# Voltage_Monitor.net
KiCad netlist of a schematic drawn in Altium Designer
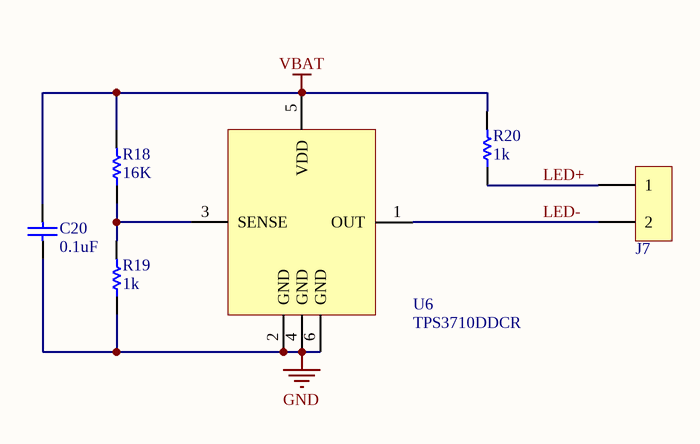
[diagram p0: Voltage Monitor.SchDoc]

(export (version "E")
  (design (tool "Eeschema 10.0.6"))
  (components
    (comp (ref "C20")
      (value "0.1uF")
      (footprint "CAPC1608X09N")
      (fields
        (field (name "DIGIKEY PART NUMBER") "490-1519-1-ND")
        (field (name "VOLTAGE") "50V")
        (field (name "TOLERANCE") "10%")
      )
      (libsource (lib "Speaker Library") (part "CAP CER 0.1uF 0603"))
    )
    (comp (ref "J7")
      (value "2POS THRU HOLE 2.54MM")
      (footprint "2POS Through Hole 2.54MM")
      (libsource (lib "Speaker Library") (part "2POS THRU HOLE 2.54MM"))
    )
    (comp (ref "R18")
      (value "16K")
      (footprint "RESC1608X06N")
      (fields
        (field (name "TOLERANCE") "1%")
        (field (name "DIGIKEY PART NUMBER") "311-16KGRCT-ND")
        (field (name "MANUFACTURER") "Yageo")
      )
      (libsource (lib "Speaker Library") (part "RES 16K 0603"))
    )
    (comp (ref "R19")
      (value "1k")
      (footprint "RESC1608X06N")
      (fields
        (field (name "TOLERANCE") "1%")
        (field (name "POWER") "0.25W")
        (field (name "MANUFACTURER") "Panasonic")
      )
      (libsource (lib "Speaker Library") (part "RES 1K 0603"))
    )
    (comp (ref "R20")
      (value "1k")
      (footprint "RESC1608X06N")
      (fields
        (field (name "TOLERANCE") "1%")
        (field (name "POWER") "0.25W")
        (field (name "MANUFACTURER") "Panasonic")
      )
      (libsource (lib "Speaker Library") (part "RES 1K 0603"))
    )
    (comp (ref "U6")
      (value "TPS3710DDCR")
      (footprint "SOT95P280X110-6N (DDC)")
      (description "Voltage Monitor, 400mV, Open Drain")
      (fields
        (field (name "MANUFACTURER") "Texas Instruments")
        (field (name "DIGIKEY PART NUMBER") "296-43105-1-ND")
      )
      (libsource (lib "Speaker Library") (part "TPS3710DDCR"))
    )
  )
  (nets
    (net (code "1") (name "/LED+") (class "Default")
      (node (ref "J7") (pin "1") (pinfunction "1_1") (pintype "passive"))
      (node (ref "R20") (pin "1") (pinfunction "1_1") (pintype "passive"))
    )
    (net (code "2") (name "/LED-") (class "Default")
      (node (ref "J7") (pin "2") (pinfunction "2_2") (pintype "passive"))
      (node (ref "U6") (pin "1") (pinfunction "OUT_1") (pintype "passive"))
    )
    (net (code "3") (name "GND") (class "Default")
      (node (ref "C20") (pin "1") (pinfunction "1_1") (pintype "passive"))
      (node (ref "R19") (pin "1") (pinfunction "1_1") (pintype "passive"))
      (node (ref "U6") (pin "2") (pinfunction "GND_2") (pintype "power_in"))
      (node (ref "U6") (pin "4") (pinfunction "GND_4") (pintype "power_in"))
      (node (ref "U6") (pin "6") (pinfunction "GND_6") (pintype "power_in"))
    )
    (net (code "4") (name "Net-(U6-SENSE)") (class "Default")
      (node (ref "R18") (pin "1") (pinfunction "1_1") (pintype "passive"))
      (node (ref "R19") (pin "2") (pinfunction "2_2") (pintype "passive"))
      (node (ref "U6") (pin "3") (pinfunction "SENSE_3") (pintype "passive"))
    )
    (net (code "5") (name "VBAT") (class "Default")
      (node (ref "C20") (pin "2") (pinfunction "2_2") (pintype "passive"))
      (node (ref "R18") (pin "2") (pinfunction "2_2") (pintype "passive"))
      (node (ref "R20") (pin "2") (pinfunction "2_2") (pintype "passive"))
      (node (ref "U6") (pin "5") (pinfunction "VDD_5") (pintype "power_in"))
    )
  )
)
